# Antenna.net
KiCad netlist of a schematic drawn in Altium Designer
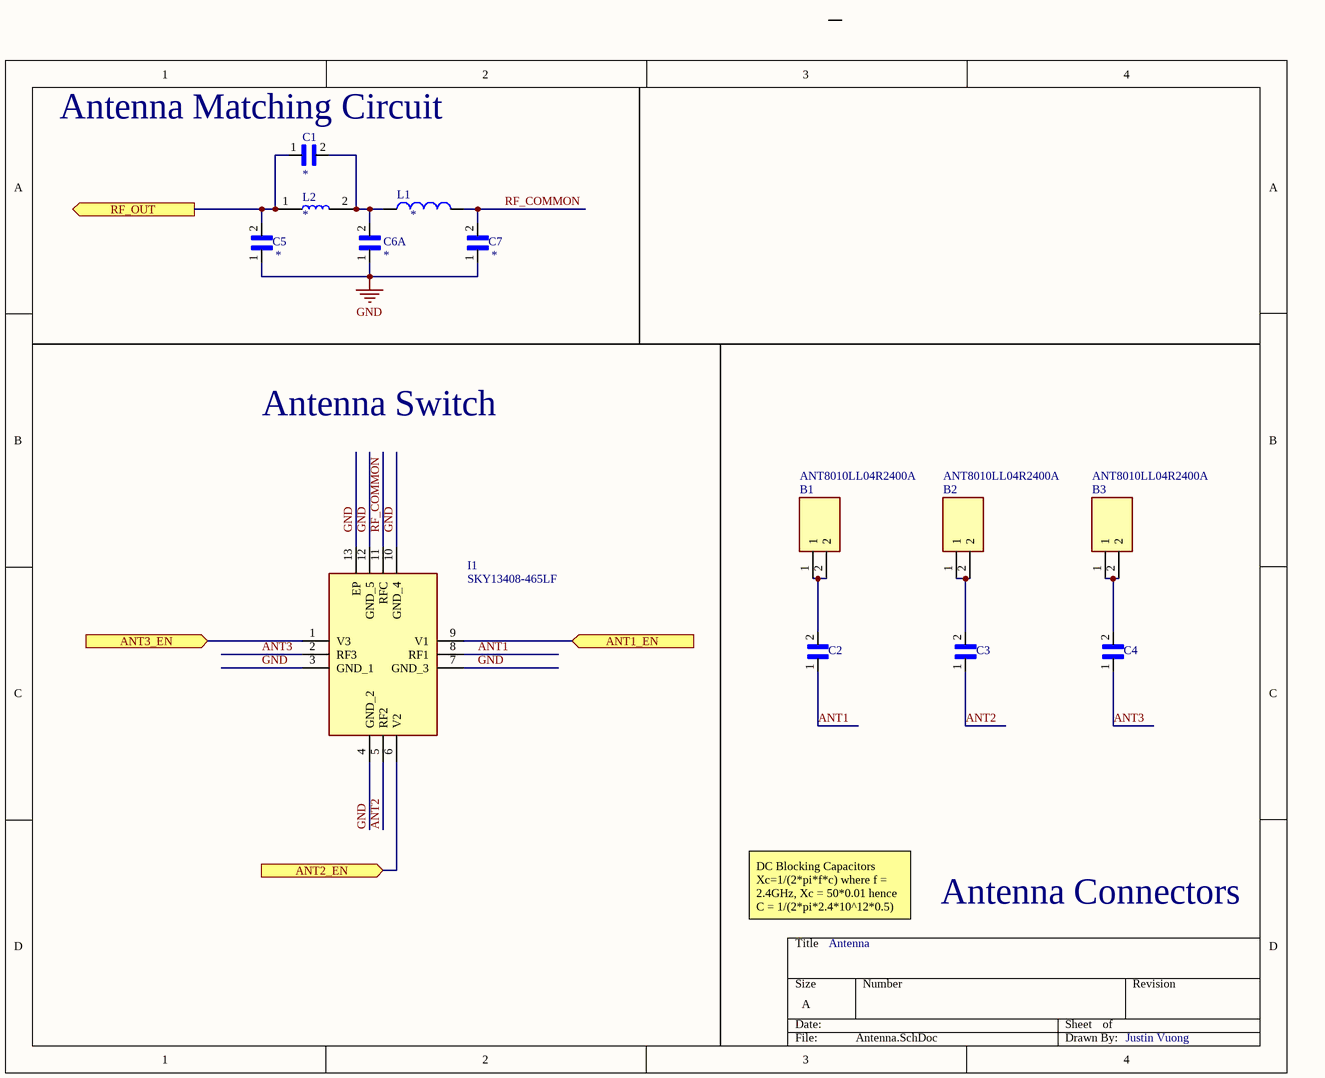
[diagram p0: Antenna.SchDoc]

(export (version "E")
  (design (tool "Eeschema 10.0.6"))
  (components
    (comp (ref "B1")
      (value "ANT8010LL04R2400A")
      (footprint "ANT8010LL04R2400A")
      (description "Antennas 2.4GHz 50 Ohm 1W CHIP ANTENNA")
      (fields (field (name "MOUSER PART NUMBER") "603-ANT8010LL04R2400"))
      (libsource (lib "ANT8010LL04R2400A") (part "ANT8010LL04R2400A"))
    )
    (comp (ref "B2")
      (value "ANT8010LL04R2400A")
      (footprint "ANT8010LL04R2400A")
      (description "Antennas 2.4GHz 50 Ohm 1W CHIP ANTENNA")
      (fields (field (name "MOUSER PART NUMBER") "603-ANT8010LL04R2400"))
      (libsource (lib "ANT8010LL04R2400A") (part "ANT8010LL04R2400A"))
    )
    (comp (ref "B3")
      (value "ANT8010LL04R2400A")
      (footprint "ANT8010LL04R2400A")
      (description "Antennas 2.4GHz 50 Ohm 1W CHIP ANTENNA")
      (fields (field (name "MOUSER PART NUMBER") "603-ANT8010LL04R2400"))
      (libsource (lib "ANT8010LL04R2400A") (part "ANT8010LL04R2400A"))
    )
    (comp (ref "C1")
      (value "GRM0335C1HR40BA01D")
      (footprint "INDC0603X33N:INDC0603X33N")
      (description "0201 50 V 0.4 pF Â±0.1 pF Tolerance C0G Monolithic Ceramic Chip Capacitor")
      (fields (field (name "ALTIUM_VALUE") "*"))
      (libsource (lib "GRM0335C1HR40BA01D") (part "GRM0335C1HR40BA01D"))
    )
    (comp (ref "C2")
      (value "GCM1555C1HR80BA16D")
      (footprint "CAPC1005X55N:CAPC1005X55N")
      (description "SMD Capacitor C0G(EIA) with Capacitance: 0.80pF Tol. 0.1pF. Rated Voltage: 50Vdc")
      (libsource (lib "GCM1555C1HR80BA16D") (part "GCM1555C1HR80BA16D"))
    )
    (comp (ref "C3")
      (value "GCM1555C1HR80BA16D")
      (footprint "CAPC1005X55N:CAPC1005X55N")
      (description "SMD Capacitor C0G(EIA) with Capacitance: 0.80pF Tol. 0.1pF. Rated Voltage: 50Vdc")
      (libsource (lib "GCM1555C1HR80BA16D") (part "GCM1555C1HR80BA16D"))
    )
    (comp (ref "C4")
      (value "GCM1555C1HR80BA16D")
      (footprint "CAPC1005X55N:CAPC1005X55N")
      (description "SMD Capacitor C0G(EIA) with Capacitance: 0.80pF Tol. 0.1pF. Rated Voltage: 50Vdc")
      (libsource (lib "GCM1555C1HR80BA16D") (part "GCM1555C1HR80BA16D"))
    )
    (comp (ref "C5")
      (value "GCM1555C1HR80BA16D")
      (footprint "CAPC1005X55N:CAPC1005X55N")
      (description "SMD Capacitor C0G(EIA) with Capacitance: 0.80pF Tol. 0.1pF. Rated Voltage: 50Vdc")
      (fields (field (name "ALTIUM_VALUE") "*"))
      (libsource (lib "GCM1555C1HR80BA16D") (part "GCM1555C1HR80BA16D"))
    )
    (comp (ref "C6")
      (value "GRM0335C1H1R6BA01D")
      (footprint "CAPC0603X33N:CAPC0603X33N")
      (description "SMD capacitor C0G(EIA) with capacitance 1.6pF Tol.0.1pF. Rated voltage 50Vdc 125C")
      (fields (field (name "MF") "Murata") (field (name "ALTIUM_VALUE") "*"))
      (libsource (lib "GRM0335C1H1R6BA01D") (part "GRM0335C1H1R6BA01D"))
    )
    (comp (ref "C7")
      (value "GRM0335C1HR60BA01D")
      (footprint "CAPC0603X33N:CAPC0603X33N")
      (description "Cap Ceramic 0.6pF 50V C0G 0.1pF Pad SMD 0201 125C T/R")
      (fields (field (name "ALTIUM_VALUE") "*"))
      (libsource (lib "GRM0335C1HR60BA01D") (part "GRM0335C1HR60BA01D"))
    )
    (comp (ref "I1")
      (value "SKY13408-465LF")
      (footprint "QFN50P200X200X65-13N-D")
      (description "RF Switch ICs 1-6GHz SP3T Typ. IIP3 54dBm")
      (fields (field (name "MOUSER PART NUMBER") "873-SKY13408-465LF"))
      (libsource (lib "SKY13408-465LF") (part "SKY13408-465LF"))
    )
    (comp (ref "L1")
      (value "LQP03TN3N0B02D")
      (footprint "INDC0603X33N:INDC0603X33N")
      (description "Inductor with Inductance: 3nH Tol. +/-0.1nH, Package: 0201 (0603)")
      (fields
        (field (name "MF") "Murata")
        (field (name "DIGI-KEY_PART_NUMBER") "490-6727-1-ND")
        (field (name "ALTIUM_VALUE") "*")
      )
      (libsource (lib "LQP03TN3N0B02D") (part "LQP03TN3N0B02D"))
    )
    (comp (ref "L2")
      (value "L-07C2N4SV6T")
      (footprint "INDC1005X60N")
      (fields (field (name "ALTIUM_VALUE") "*"))
      (libsource (lib "L-07C2N4SV6T") (part "L-07C2N4SV6T"))
    )
  )
  (nets
    (net (code "1") (name "/ANT1") (class "Default")
      (node (ref "C2") (pin "1") (pinfunction "1_1") (pintype "passive"))
      (node (ref "I1") (pin "8") (pinfunction "RF1_8") (pintype "passive"))
    )
    (net (code "2") (name "/ANT1_EN") (class "Default")
      (node (ref "I1") (pin "9") (pinfunction "V1_9") (pintype "passive"))
    )
    (net (code "3") (name "/ANT2") (class "Default")
      (node (ref "C3") (pin "1") (pinfunction "1_1") (pintype "passive"))
      (node (ref "I1") (pin "5") (pinfunction "RF2_5") (pintype "passive"))
    )
    (net (code "4") (name "/ANT2_EN") (class "Default")
      (node (ref "I1") (pin "6") (pinfunction "V2_6") (pintype "passive"))
    )
    (net (code "5") (name "/ANT3") (class "Default")
      (node (ref "C4") (pin "1") (pinfunction "1_1") (pintype "passive"))
      (node (ref "I1") (pin "2") (pinfunction "RF3_2") (pintype "passive"))
    )
    (net (code "6") (name "/ANT3_EN") (class "Default")
      (node (ref "I1") (pin "1") (pinfunction "V3_1") (pintype "passive"))
    )
    (net (code "7") (name "/RF_COMMON") (class "Default")
      (node (ref "C7") (pin "2") (pinfunction "2_2") (pintype "passive"))
      (node (ref "I1") (pin "11") (pinfunction "RFC_11") (pintype "passive"))
      (node (ref "L1") (pin "2") (pinfunction "2_2") (pintype "passive"))
    )
    (net (code "8") (name "/RF_OUT") (class "Default")
      (node (ref "C1") (pin "1") (pinfunction "1_1") (pintype "passive"))
      (node (ref "C5") (pin "2") (pinfunction "2_2") (pintype "passive"))
      (node (ref "L2") (pin "1") (pinfunction "1_1") (pintype "passive"))
    )
    (net (code "9") (name "GND") (class "Default")
      (node (ref "C5") (pin "1") (pinfunction "1_1") (pintype "passive"))
      (node (ref "C6") (pin "1") (pinfunction "1_1") (pintype "passive"))
      (node (ref "C7") (pin "1") (pinfunction "1_1") (pintype "passive"))
      (node (ref "I1") (pin "10") (pinfunction "GND_4_10") (pintype "passive"))
      (node (ref "I1") (pin "12") (pinfunction "GND_5_12") (pintype "passive"))
      (node (ref "I1") (pin "13") (pinfunction "EP_13") (pintype "passive"))
      (node (ref "I1") (pin "3") (pinfunction "GND_1_3") (pintype "passive"))
      (node (ref "I1") (pin "4") (pinfunction "GND_2_4") (pintype "passive"))
      (node (ref "I1") (pin "7") (pinfunction "GND_3_7") (pintype "passive"))
    )
    (net (code "10") (name "Net-(B1-Pad1)") (class "Default")
      (node (ref "B1") (pin "1") (pinfunction "1_1") (pintype "passive"))
      (node (ref "B1") (pin "2") (pinfunction "2_2") (pintype "passive"))
      (node (ref "C2") (pin "2") (pinfunction "2_2") (pintype "passive"))
    )
    (net (code "11") (name "Net-(B2-Pad1)") (class "Default")
      (node (ref "B2") (pin "1") (pinfunction "1_1") (pintype "passive"))
      (node (ref "B2") (pin "2") (pinfunction "2_2") (pintype "passive"))
      (node (ref "C3") (pin "2") (pinfunction "2_2") (pintype "passive"))
    )
    (net (code "12") (name "Net-(B3-Pad1)") (class "Default")
      (node (ref "B3") (pin "1") (pinfunction "1_1") (pintype "passive"))
      (node (ref "B3") (pin "2") (pinfunction "2_2") (pintype "passive"))
      (node (ref "C4") (pin "2") (pinfunction "2_2") (pintype "passive"))
    )
    (net (code "13") (name "Net-(C1-Pad2)") (class "Default")
      (node (ref "C1") (pin "2") (pinfunction "2_2") (pintype "passive"))
      (node (ref "C6") (pin "2") (pinfunction "2_2") (pintype "passive"))
      (node (ref "L1") (pin "1") (pinfunction "1_1") (pintype "passive"))
      (node (ref "L2") (pin "2") (pinfunction "2_2") (pintype "passive"))
    )
  )
)
